# ST-LINK_V2-1.net
KiCad netlist of a schematic drawn in Altium Designer
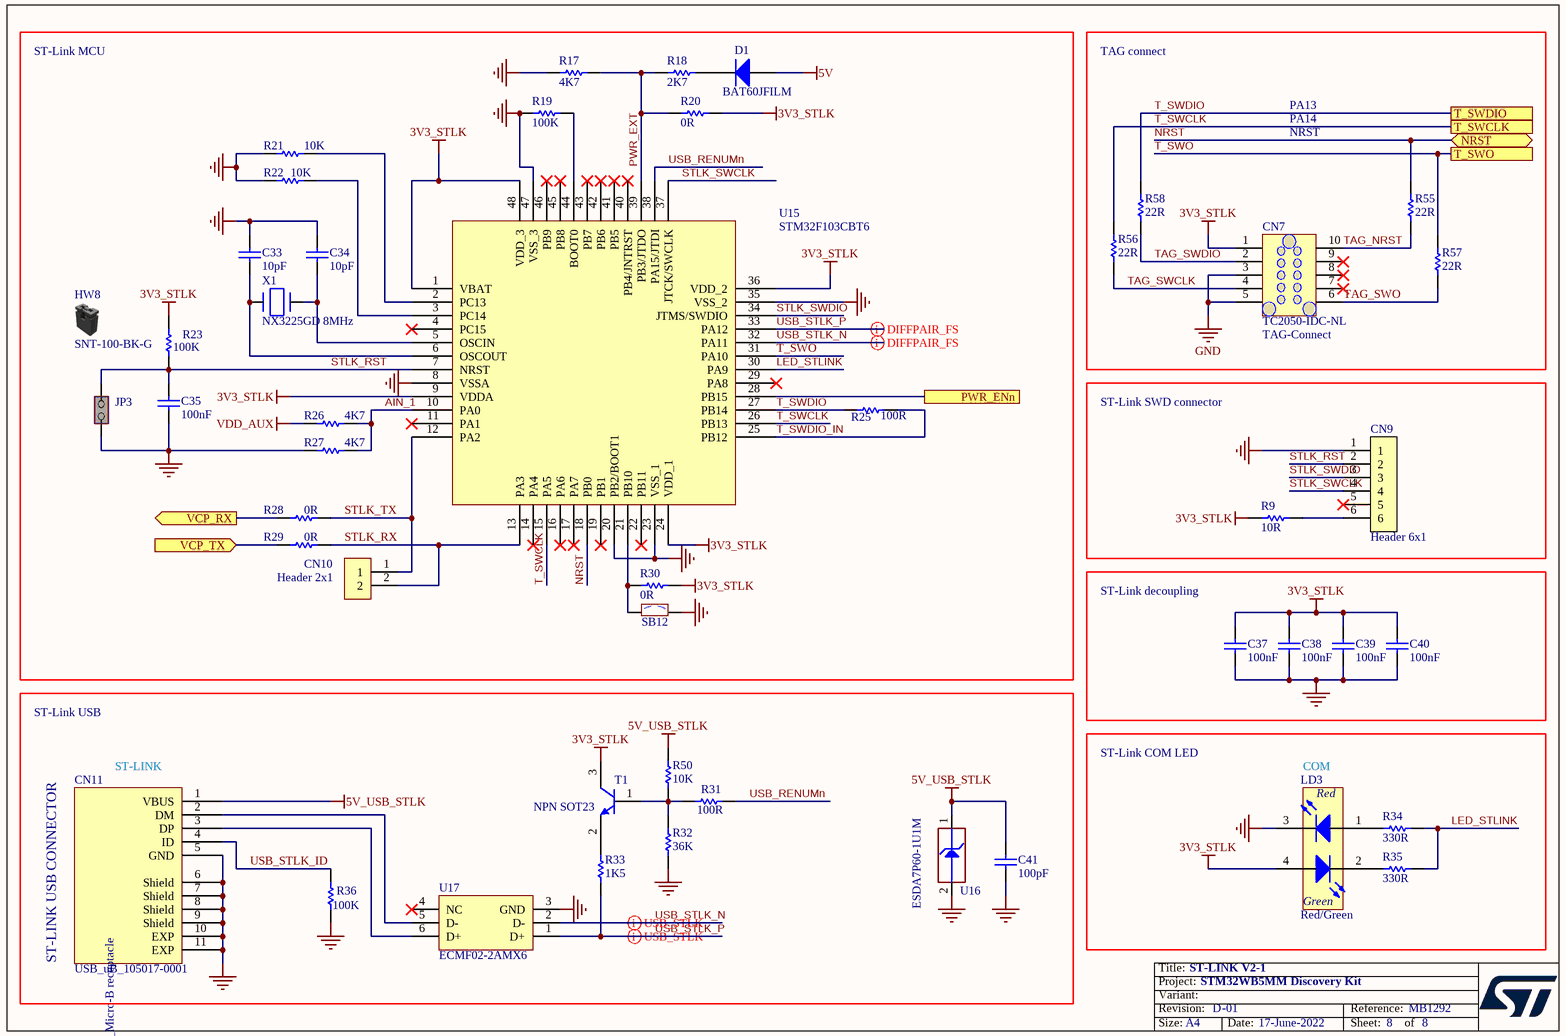
[diagram p0: ST-LINK_V2-1.SchDoc]

(export (version "E")
  (design (tool "Eeschema 10.0.6"))
  (components
    (comp (ref "C33")
      (value "10pF")
      (footprint "C0402")
      (description "Capacitor, MLCC, 10pF, 50V, NPO, +/-5%, 0402, T=0,5mm")
      (fields
        (field (name "INTERNAL_PART_NUMBER") "MCD-00015")
        (field (name "MANUFACTURER_PART_NUMBER") "CC0402JRNPO9BN100")
      )
      (libsource (lib "MCD_PARTS_database") (part "Capacitor"))
    )
    (comp (ref "C34")
      (value "10pF")
      (footprint "C0402")
      (description "Capacitor, MLCC, 10pF, 50V, NPO, +/-5%, 0402, T=0,5mm")
      (fields
        (field (name "INTERNAL_PART_NUMBER") "MCD-00015")
        (field (name "MANUFACTURER_PART_NUMBER") "CC0402JRNPO9BN100")
      )
      (libsource (lib "MCD_PARTS_database") (part "Capacitor"))
    )
    (comp (ref "C35")
      (value "100nF")
      (footprint "C0402")
      (description "Capacitor, MLCC, 100nF, 16V, X7R, +/-10%, 0402, T=0.5mm")
      (fields
        (field (name "INTERNAL_PART_NUMBER") "MCD-00006")
        (field (name "MANUFACTURER_PART_NUMBER") "CC0402KRX7R7BB104")
      )
      (libsource (lib "MCD_PARTS_database") (part "Capacitor"))
    )
    (comp (ref "C37")
      (value "100nF")
      (footprint "C0402")
      (description "Capacitor, MLCC, 100nF, 16V, X7R, +/-10%, 0402, T=0.5mm")
      (fields
        (field (name "INTERNAL_PART_NUMBER") "MCD-00006")
        (field (name "MANUFACTURER_PART_NUMBER") "CC0402KRX7R7BB104")
      )
      (libsource (lib "MCD_PARTS_database") (part "Capacitor"))
    )
    (comp (ref "C38")
      (value "100nF")
      (footprint "C0402")
      (description "Capacitor, MLCC, 100nF, 16V, X7R, +/-10%, 0402, T=0.5mm")
      (fields
        (field (name "INTERNAL_PART_NUMBER") "MCD-00006")
        (field (name "MANUFACTURER_PART_NUMBER") "CC0402KRX7R7BB104")
      )
      (libsource (lib "MCD_PARTS_database") (part "Capacitor"))
    )
    (comp (ref "C39")
      (value "100nF")
      (footprint "C0402")
      (description "Capacitor, MLCC, 100nF, 16V, X7R, +/-10%, 0402, T=0.5mm")
      (fields
        (field (name "INTERNAL_PART_NUMBER") "MCD-00006")
        (field (name "MANUFACTURER_PART_NUMBER") "CC0402KRX7R7BB104")
      )
      (libsource (lib "MCD_PARTS_database") (part "Capacitor"))
    )
    (comp (ref "C40")
      (value "100nF")
      (footprint "C0402")
      (description "Capacitor, MLCC, 100nF, 16V, X7R, +/-10%, 0402, T=0.5mm")
      (fields
        (field (name "INTERNAL_PART_NUMBER") "MCD-00006")
        (field (name "MANUFACTURER_PART_NUMBER") "CC0402KRX7R7BB104")
      )
      (libsource (lib "MCD_PARTS_database") (part "Capacitor"))
    )
    (comp (ref "C41")
      (value "100pF")
      (footprint "C0603_H0P8")
      (description "Capacitor,MLCC,100pF 50V,NPO,+/-5%, 0603,T=0,8mm")
      (fields
        (field (name "INTERNAL_PART_NUMBER") "MCD-01648")
        (field (name "MANUFACTURER_PART_NUMBER") "CC0603JRNPO9BN101")
      )
      (libsource (lib "MCD_PARTS_database") (part "Capacitor"))
    )
    (comp (ref "CN7")
      (value "TC2050-IDC-NL")
      (footprint "CON_TAG-C_TC2050-IDC-NL")
      (description "Tag_Connector Header, 10x2, No legs")
      (fields
        (field (name "INTERNAL_PART_NUMBER") "MCD-00031")
        (field (name "MANUFACTURER_PART_NUMBER") "TC2050-IDC-NL-FP")
      )
      (libsource (lib "MCD_PARTS_database") (part "Tag-10-C"))
    )
    (comp (ref "CN9")
      (value "Header 6x1")
      (footprint "CON_SAMTEC_TSW-106-14-G-S")
      (description "Header 6x1, 2,54mm, height 10.67mm")
      (fields
        (field (name "INTERNAL_PART_NUMBER") "MCD-01592")
        (field (name "MANUFACTURER_PART_NUMBER") "TSW-106-14-G-S")
      )
      (libsource (lib "MCD_PARTS_database") (part "Header 6x1"))
    )
    (comp (ref "CN10")
      (value "Header 2x1")
      (footprint "CON_SAMTEC_TSW-102-07-G-S")
      (description "Header, 2x1, 2,54mm, VR, TH, Height 5.84mm/2.54mm")
      (fields
        (field (name "INTERNAL_PART_NUMBER") "MCD-00032")
        (field (name "MANUFACTURER_PART_NUMBER") "TSW-102-07-G-S")
      )
      (libsource (lib "MCD_PARTS_database") (part "Header 2x1"))
    )
    (comp (ref "CN11")
      (value "USB_uB_105017-0001")
      (footprint "CON_USBMICROB_MOLEX_105017-0001_H2P90")
      (description "USB-MICRO-B, 0.65mm, RA, SMT, Bottom Mount,")
      (fields
        (field (name "INTERNAL_PART_NUMBER") "MCD-00028")
        (field (name "MANUFACTURER_PART_NUMBER") "1050170001")
      )
      (libsource (lib "MCD_PARTS_database") (part "USB_uB_105017.0001"))
    )
    (comp (ref "D1")
      (value "BAT60JFILM")
      (footprint "DIO_SOD323")
      (fields
        (field (name "INTERNAL_PART_NUMBER") "MCD-00034")
        (field (name "MANUFACTURER") "STMICROELECTRONICS")
        (field (name "BMS_PART_NUMBER") "9151097")
      )
      (libsource (lib "MCD_PARTS_database") (part "BAT60JFILM"))
    )
    (comp (ref "HW8")
      (value "SNT-100-BK-G")
      (description "Shunt, 2.54mm, Black, 4.3A, 6.1mm, 5mR")
      (fields (field (name "INTERNAL_PART_NUMBER") "MCD-00122") (field (name "MANUFACTURER") "SAMTEC"))
      (libsource (lib "MCD_PARTS_database") (part "Shunt Black 2.54mm"))
    )
    (comp (ref "JP3")
      (value "Jumper_Header 2x1 Fitted")
      (footprint "CON_SAMTEC_TSW-102-07-G-S")
      (description "Header, 2x1, 2,54mm, VR, TH, Height 5.84mm/2.54mm - Shunt Fitted by default")
      (fields
        (field (name "INTERNAL_PART_NUMBER") "MCD-01904")
        (field (name "MANUFACTURER_PART_NUMBER") "TSW-102-07-G-S")
      )
      (libsource (lib "MCD_PARTS_database") (part "Jumper_Header 2x1 Fitted"))
    )
    (comp (ref "LD3")
      (value "Red/Green")
      (footprint "LED_BI-GR_WE-150141SV73110")
      (description "LED Bicolor, Red/Green, 2V, 20mA, 4-PLCC")
      (fields
        (field (name "INTERNAL_PART_NUMBER") "MCD-02631")
        (field (name "MANUFACTURER") "WURTH ELEKTRONIK")
      )
      (libsource (lib "MCD_PARTS_database") (part "LED_BICOLOR"))
    )
    (comp (ref "R9")
      (value "10R")
      (footprint "R0402")
      (description "Resistor,10R,0402,1%,1/16W")
      (fields
        (field (name "INTERNAL_PART_NUMBER") "MCD-00358")
        (field (name "MANUFACTURER_PART_NUMBER") "RC0402FR-0710RL")
      )
      (libsource (lib "MCD_PARTS_database") (part "Resistor"))
    )
    (comp (ref "R17")
      (value "4K7")
      (footprint "R0402")
      (description "Resistor,4K7,0402,1%,1/16W")
      (fields
        (field (name "INTERNAL_PART_NUMBER") "MCD-00065")
        (field (name "MANUFACTURER_PART_NUMBER") "RC0402FR-074K7L")
      )
      (libsource (lib "MCD_PARTS_database") (part "Resistor"))
    )
    (comp (ref "R18")
      (value "2K7")
      (footprint "R0402")
      (description "Resistor,2K7,0402,1%,1/16W")
      (fields
        (field (name "INTERNAL_PART_NUMBER") "MCD-00055")
        (field (name "MANUFACTURER_PART_NUMBER") "RC0402FR-072K7L")
      )
      (libsource (lib "MCD_PARTS_database") (part "Resistor"))
    )
    (comp (ref "R19")
      (value "100K")
      (footprint "R0402")
      (description "Resistor,100K,0402,1%,1/16W")
      (fields
        (field (name "INTERNAL_PART_NUMBER") "MCD-00059")
        (field (name "MANUFACTURER_PART_NUMBER") "RC0402FR-07100KL")
      )
      (libsource (lib "MCD_PARTS_database") (part "Resistor"))
    )
    (comp (ref "R20")
      (value "0R")
      (footprint "R0402")
      (description "Resistor,0R,0402,5%,1/16W")
      (fields
        (field (name "INTERNAL_PART_NUMBER") "MCD-00052")
        (field (name "MANUFACTURER_PART_NUMBER") "RC0402JR-070RL")
      )
      (libsource (lib "MCD_PARTS_database") (part "Resistor"))
    )
    (comp (ref "R21")
      (value "10K")
      (footprint "R0402")
      (description "Resistor,10K,0402,1%,1/16W")
      (fields
        (field (name "INTERNAL_PART_NUMBER") "MCD-00053")
        (field (name "MANUFACTURER_PART_NUMBER") "RC0402FR-0710KL")
      )
      (libsource (lib "MCD_PARTS_database") (part "Resistor"))
    )
    (comp (ref "R22")
      (value "10K")
      (footprint "R0402")
      (description "Resistor,10K,0402,1%,1/16W")
      (fields
        (field (name "INTERNAL_PART_NUMBER") "MCD-00053")
        (field (name "MANUFACTURER_PART_NUMBER") "RC0402FR-0710KL")
      )
      (libsource (lib "MCD_PARTS_database") (part "Resistor"))
    )
    (comp (ref "R23")
      (value "100K")
      (footprint "R0402")
      (description "Resistor,100K,0402,1%,1/16W")
      (fields
        (field (name "INTERNAL_PART_NUMBER") "MCD-00059")
        (field (name "MANUFACTURER_PART_NUMBER") "RC0402FR-07100KL")
      )
      (libsource (lib "MCD_PARTS_database") (part "Resistor"))
    )
    (comp (ref "R25")
      (value "100R")
      (footprint "R0402")
      (description "Resistor,100R,0402,1%,1/16W")
      (fields
        (field (name "INTERNAL_PART_NUMBER") "MCD-00067")
        (field (name "MANUFACTURER_PART_NUMBER") "RC0402FR-07100RL")
      )
      (libsource (lib "MCD_PARTS_database") (part "Resistor"))
    )
    (comp (ref "R26")
      (value "4K7")
      (footprint "R0402")
      (description "Resistor,4K7,0402,1%,1/16W")
      (fields
        (field (name "INTERNAL_PART_NUMBER") "MCD-00065")
        (field (name "MANUFACTURER_PART_NUMBER") "RC0402FR-074K7L")
      )
      (libsource (lib "MCD_PARTS_database") (part "Resistor"))
    )
    (comp (ref "R27")
      (value "4K7")
      (footprint "R0402")
      (description "Resistor,4K7,0402,1%,1/16W")
      (fields
        (field (name "INTERNAL_PART_NUMBER") "MCD-00065")
        (field (name "MANUFACTURER_PART_NUMBER") "RC0402FR-074K7L")
      )
      (libsource (lib "MCD_PARTS_database") (part "Resistor"))
    )
    (comp (ref "R28")
      (value "0R")
      (footprint "R0402")
      (description "Resistor,0R,0402,5%,1/16W")
      (fields
        (field (name "INTERNAL_PART_NUMBER") "MCD-00052")
        (field (name "MANUFACTURER_PART_NUMBER") "RC0402JR-070RL")
      )
      (libsource (lib "MCD_PARTS_database") (part "Resistor"))
    )
    (comp (ref "R29")
      (value "0R")
      (footprint "R0402")
      (description "Resistor,0R,0402,5%,1/16W")
      (fields
        (field (name "INTERNAL_PART_NUMBER") "MCD-00052")
        (field (name "MANUFACTURER_PART_NUMBER") "RC0402JR-070RL")
      )
      (libsource (lib "MCD_PARTS_database") (part "Resistor"))
    )
    (comp (ref "R30")
      (value "0R")
      (footprint "R0402")
      (description "Resistor,0R,0402,5%,1/16W")
      (fields
        (field (name "INTERNAL_PART_NUMBER") "MCD-00052")
        (field (name "MANUFACTURER_PART_NUMBER") "RC0402JR-070RL")
      )
      (libsource (lib "MCD_PARTS_database") (part "Resistor"))
    )
    (comp (ref "R31")
      (value "100R")
      (footprint "R0402")
      (description "Resistor,100R,0402,1%,1/16W")
      (fields
        (field (name "INTERNAL_PART_NUMBER") "MCD-00067")
        (field (name "MANUFACTURER_PART_NUMBER") "RC0402FR-07100RL")
      )
      (libsource (lib "MCD_PARTS_database") (part "Resistor"))
    )
    (comp (ref "R32")
      (value "36K")
      (footprint "R0402")
      (description "Resistor,36K,0402,1%,1/16W")
      (fields
        (field (name "INTERNAL_PART_NUMBER") "MCD-00069")
        (field (name "MANUFACTURER_PART_NUMBER") "RC0402FR-0736KL")
      )
      (libsource (lib "MCD_PARTS_database") (part "Resistor"))
    )
    (comp (ref "R33")
      (value "1K5")
      (footprint "R0402")
      (description "Resistor,1K5,0402,1%,1/16W")
      (fields
        (field (name "INTERNAL_PART_NUMBER") "MCD-00068")
        (field (name "MANUFACTURER_PART_NUMBER") "RC0402FR-071K5L")
      )
      (libsource (lib "MCD_PARTS_database") (part "Resistor"))
    )
    (comp (ref "R34")
      (value "330R")
      (footprint "R0402")
      (description "Resistor,330R,0402,1%,1/16W")
      (fields
        (field (name "INTERNAL_PART_NUMBER") "MCD-00062")
        (field (name "MANUFACTURER_PART_NUMBER") "RC0402FR-07330RL")
      )
      (libsource (lib "MCD_PARTS_database") (part "Resistor"))
    )
    (comp (ref "R35")
      (value "330R")
      (footprint "R0402")
      (description "Resistor,330R,0402,1%,1/16W")
      (fields
        (field (name "INTERNAL_PART_NUMBER") "MCD-00062")
        (field (name "MANUFACTURER_PART_NUMBER") "RC0402FR-07330RL")
      )
      (libsource (lib "MCD_PARTS_database") (part "Resistor"))
    )
    (comp (ref "R36")
      (value "100K")
      (footprint "R0402")
      (description "Resistor,100K,0402,1%,1/16W")
      (fields
        (field (name "INTERNAL_PART_NUMBER") "MCD-00059")
        (field (name "MANUFACTURER_PART_NUMBER") "RC0402FR-07100KL")
      )
      (libsource (lib "MCD_PARTS_database") (part "Resistor"))
    )
    (comp (ref "R50")
      (value "10K")
      (footprint "R0402")
      (description "Resistor,10K,0402,1%,1/16W")
      (fields
        (field (name "INTERNAL_PART_NUMBER") "MCD-00053")
        (field (name "MANUFACTURER_PART_NUMBER") "RC0402FR-0710KL")
      )
      (libsource (lib "MCD_PARTS_database") (part "Resistor"))
    )
    (comp (ref "R55")
      (value "22R")
      (footprint "R0402")
      (description "Resistor,22R,0402,1%,1/16W")
      (fields
        (field (name "INTERNAL_PART_NUMBER") "MCD-00189")
        (field (name "MANUFACTURER_PART_NUMBER") "RC0402FR-0722RL")
      )
      (libsource (lib "MCD_PARTS_database") (part "Resistor"))
    )
    (comp (ref "R56")
      (value "22R")
      (footprint "R0402")
      (description "Resistor,22R,0402,1%,1/16W")
      (fields
        (field (name "INTERNAL_PART_NUMBER") "MCD-00189")
        (field (name "MANUFACTURER_PART_NUMBER") "RC0402FR-0722RL")
      )
      (libsource (lib "MCD_PARTS_database") (part "Resistor"))
    )
    (comp (ref "R57")
      (value "22R")
      (footprint "R0402")
      (description "Resistor,22R,0402,1%,1/16W")
      (fields
        (field (name "INTERNAL_PART_NUMBER") "MCD-00189")
        (field (name "MANUFACTURER_PART_NUMBER") "RC0402FR-0722RL")
      )
      (libsource (lib "MCD_PARTS_database") (part "Resistor"))
    )
    (comp (ref "R58")
      (value "22R")
      (footprint "R0402")
      (description "Resistor,22R,0402,1%,1/16W")
      (fields
        (field (name "INTERNAL_PART_NUMBER") "MCD-00189")
        (field (name "MANUFACTURER_PART_NUMBER") "RC0402FR-0722RL")
      )
      (libsource (lib "MCD_PARTS_database") (part "Resistor"))
    )
    (comp (ref "SB12")
      (value "SB_OFF")
      (footprint "SOLDER-BRIDGE_R0603-0R")
      (description "Solder Bridge OFF")
      (fields
        (field (name "INTERNAL_PART_NUMBER") "MCD-00072")
        (field (name "MANUFACTURER_PART_NUMBER") "RC0603JR-070RL")
      )
      (libsource (lib "MCD_PARTS_database") (part "SB_OFF"))
    )
    (comp (ref "T1")
      (value "NPN SOT23")
      (footprint "NPN_SOT23")
      (description "NPN Bipolar Transistor")
      (fields
        (field (name "INTERNAL_PART_NUMBER") "MCD-00073")
        (field (name "MANUFACTURER_PART_NUMBER") "BSR14")
      )
      (libsource (lib "MCD_PARTS_database") (part "9013-SOT23"))
    )
    (comp (ref "U15")
      (value "STM32F103CBT6")
      (footprint "ICC_LQFP48_7X7_P050")
      (description "Medium-density performance line ARM-based 32-bit MCU with 128KB Flash")
      (fields
        (field (name "INTERNAL_PART_NUMBER") "MCD-00085")
        (field (name "MANUFACTURER") "STMICROELECTRONICS")
      )
      (libsource (lib "MCD_PARTS_database") (part "STM32F103CBT6"))
    )
    (comp (ref "U16")
      (value "ESDA7P60-1U1M")
      (footprint "ESD_QFN2_1P6X1_P125")
      (description "High power transient voltage suppressor, 7V breakdown")
      (fields
        (field (name "INTERNAL_PART_NUMBER") "MCD-00251")
        (field (name "MANUFACTURER") "STMICROELECTRONICS")
      )
      (libsource (lib "MCD_PARTS_database") (part "ESD-TRANSIL"))
    )
    (comp (ref "U17")
      (value "ECMF02-2AMX6")
      (footprint "ESD_QFN-6L_1P7X1P5_P050")
      (description "Common mode filter with ESD protection for USB 2.0 interface")
      (fields
        (field (name "INTERNAL_PART_NUMBER") "MCD-00649")
        (field (name "MANUFACTURER") "STMICROELECTRONICS")
      )
      (libsource (lib "MCD_PARTS_database") (part "ECMF02-2AMX6"))
    )
    (comp (ref "X1")
      (value "NX3225GD 8MHz")
      (footprint "CRY_NX3225GD_2P")
      (description "Crystal 8MHz, 8pF, +-20ppm, 500ohms max,  SMD")
      (fields
        (field (name "INTERNAL_PART_NUMBER") "MCD-00092")
        (field (name "MANUFACTURER_PART_NUMBER") "NX3225GD 8MHz EXS00A-CG04874")
      )
      (libsource (lib "MCD_PARTS_database") (part "XTAL_2_PINS"))
    )
  )
  (nets
    (net (code "1") (name "/AIN_1") (class "Default")
      (node (ref "R26") (pin "2") (pinfunction "2_2") (pintype "passive"))
      (node (ref "R27") (pin "2") (pinfunction "2_2") (pintype "passive"))
      (node (ref "U15") (pin "10") (pinfunction "PA0_10") (pintype "passive"))
    )
    (net (code "2") (name "/LED_STLINK") (class "Default")
      (node (ref "R34") (pin "2") (pinfunction "2_2") (pintype "passive"))
      (node (ref "R35") (pin "2") (pinfunction "2_2") (pintype "passive"))
      (node (ref "U15") (pin "30") (pinfunction "PA9_30") (pintype "passive"))
    )
    (net (code "3") (name "/NRST") (class "Default")
      (node (ref "R55") (pin "2") (pinfunction "2_2") (pintype "passive"))
      (node (ref "U15") (pin "18") (pinfunction "PB0_18") (pintype "passive"))
    )
    (net (code "4") (name "/PWR_ENn") (class "Default")
      (node (ref "U15") (pin "28") (pinfunction "PB15_28") (pintype "passive"))
    )
    (net (code "5") (name "/PWR_EXT") (class "Default")
      (node (ref "R17") (pin "2") (pinfunction "2_2") (pintype "passive"))
      (node (ref "R18") (pin "1") (pinfunction "1_1") (pintype "passive"))
      (node (ref "R20") (pin "1") (pinfunction "1_1") (pintype "passive"))
      (node (ref "U15") (pin "39") (pinfunction "PB3/JTDO_39") (pintype "passive"))
    )
    (net (code "6") (name "/STLK_RST") (class "Default")
      (node (ref "C35") (pin "2") (pinfunction "2_2") (pintype "passive"))
      (node (ref "CN9") (pin "2") (pinfunction "2_2") (pintype "passive"))
      (node (ref "JP3") (pin "1") (pinfunction "COMMON_1") (pintype "passive"))
      (node (ref "R23") (pin "1") (pinfunction "1_1") (pintype "passive"))
      (node (ref "U15") (pin "7") (pinfunction "NRST_7") (pintype "passive"))
    )
    (net (code "7") (name "/STLK_RX") (class "Default")
      (node (ref "CN10") (pin "2") (pinfunction "2_2") (pintype "passive"))
      (node (ref "R29") (pin "2") (pinfunction "2_2") (pintype "passive"))
      (node (ref "U15") (pin "13") (pinfunction "PA3_13") (pintype "passive"))
    )
    (net (code "8") (name "/STLK_SWCLK") (class "Default")
      (node (ref "CN9") (pin "4") (pinfunction "4_4") (pintype "passive"))
      (node (ref "U15") (pin "37") (pinfunction "JTCK/SWCLK_37") (pintype "passive"))
    )
    (net (code "9") (name "/STLK_SWDIO") (class "Default")
      (node (ref "CN9") (pin "3") (pinfunction "3_3") (pintype "passive"))
      (node (ref "U15") (pin "34") (pinfunction "JTMS/SWDIO_34") (pintype "passive"))
    )
    (net (code "10") (name "/STLK_TX") (class "Default")
      (node (ref "CN10") (pin "1") (pinfunction "1_1") (pintype "passive"))
      (node (ref "R28") (pin "1") (pinfunction "1_1") (pintype "passive"))
      (node (ref "U15") (pin "12") (pinfunction "PA2_12") (pintype "passive"))
    )
    (net (code "11") (name "/TAG_NRST") (class "Default")
      (node (ref "CN7") (pin "10") (pinfunction "10_10") (pintype "passive"))
      (node (ref "R55") (pin "1") (pinfunction "1_1") (pintype "passive"))
    )
    (net (code "12") (name "/TAG_SWCLK") (class "Default")
      (node (ref "CN7") (pin "4") (pinfunction "4_4") (pintype "passive"))
      (node (ref "R56") (pin "1") (pinfunction "1_1") (pintype "passive"))
    )
    (net (code "13") (name "/TAG_SWDIO") (class "Default")
      (node (ref "CN7") (pin "2") (pinfunction "2_2") (pintype "passive"))
      (node (ref "R58") (pin "1") (pinfunction "1_1") (pintype "passive"))
    )
    (net (code "14") (name "/TAG_SWO") (class "Default")
      (node (ref "CN7") (pin "6") (pinfunction "6_6") (pintype "passive"))
      (node (ref "R57") (pin "2") (pinfunction "2_2") (pintype "passive"))
    )
    (net (code "15") (name "/T_SWCLK") (class "Default")
      (node (ref "R56") (pin "2") (pinfunction "2_2") (pintype "passive"))
      (node (ref "U15") (pin "15") (pinfunction "PA5_15") (pintype "passive"))
      (node (ref "U15") (pin "26") (pinfunction "PB13_26") (pintype "passive"))
    )
    (net (code "16") (name "/T_SWDIO") (class "Default")
      (node (ref "R25") (pin "1") (pinfunction "1_1") (pintype "passive"))
      (node (ref "R58") (pin "2") (pinfunction "2_2") (pintype "passive"))
      (node (ref "U15") (pin "27") (pinfunction "PB14_27") (pintype "passive"))
    )
    (net (code "17") (name "/T_SWDIO_IN") (class "Default")
      (node (ref "R25") (pin "2") (pinfunction "2_2") (pintype "passive"))
      (node (ref "U15") (pin "25") (pinfunction "PB12_25") (pintype "passive"))
    )
    (net (code "18") (name "/T_SWO") (class "Default")
      (node (ref "R57") (pin "1") (pinfunction "1_1") (pintype "passive"))
      (node (ref "U15") (pin "31") (pinfunction "PA10_31") (pintype "passive"))
    )
    (net (code "19") (name "/USB_RENUMn") (class "Default")
      (node (ref "R31") (pin "2") (pinfunction "2_2") (pintype "passive"))
      (node (ref "U15") (pin "38") (pinfunction "PA15/JTDI_38") (pintype "passive"))
    )
    (net (code "20") (name "/USB_STLK_ID") (class "Default")
      (node (ref "CN11") (pin "4") (pinfunction "ID_4") (pintype "passive"))
      (node (ref "R36") (pin "2") (pinfunction "2_2") (pintype "passive"))
    )
    (net (code "21") (name "/USB_STLK_N") (class "Default")
      (node (ref "U15") (pin "32") (pinfunction "PA11_32") (pintype "passive"))
      (node (ref "U17") (pin "2") (pinfunction "D-_2") (pintype "passive"))
    )
    (net (code "22") (name "/USB_STLK_P") (class "Default")
      (node (ref "R33") (pin "1") (pinfunction "1_1") (pintype "passive"))
      (node (ref "U15") (pin "33") (pinfunction "PA12_33") (pintype "passive"))
      (node (ref "U17") (pin "1") (pinfunction "D+_1") (pintype "passive"))
    )
    (net (code "23") (name "/VCP_RX") (class "Default")
      (node (ref "R28") (pin "2") (pinfunction "2_2") (pintype "passive"))
    )
    (net (code "24") (name "/VCP_TX") (class "Default")
      (node (ref "R29") (pin "1") (pinfunction "1_1") (pintype "passive"))
    )
    (net (code "25") (name "3V3_STLK") (class "Default")
      (node (ref "C37") (pin "2") (pinfunction "2_2") (pintype "passive"))
      (node (ref "C38") (pin "2") (pinfunction "2_2") (pintype "passive"))
      (node (ref "C39") (pin "2") (pinfunction "2_2") (pintype "passive"))
      (node (ref "C40") (pin "2") (pinfunction "2_2") (pintype "passive"))
      (node (ref "CN7") (pin "1") (pinfunction "1_1") (pintype "passive"))
      (node (ref "LD3") (pin "4") (pinfunction "Green_anode_4") (pintype "passive"))
      (node (ref "R20") (pin "2") (pinfunction "2_2") (pintype "passive"))
      (node (ref "R23") (pin "2") (pinfunction "2_2") (pintype "passive"))
      (node (ref "R30") (pin "2") (pinfunction "2_2") (pintype "passive"))
      (node (ref "R9") (pin "1") (pinfunction "1_1") (pintype "passive"))
      (node (ref "T1") (pin "3") (pinfunction "C_3") (pintype "passive"))
      (node (ref "U15") (pin "1") (pinfunction "VBAT_1") (pintype "passive"))
      (node (ref "U15") (pin "24") (pinfunction "VDD_1_24") (pintype "passive"))
      (node (ref "U15") (pin "36") (pinfunction "VDD_2_36") (pintype "passive"))
      (node (ref "U15") (pin "48") (pinfunction "VDD_3_48") (pintype "passive"))
      (node (ref "U15") (pin "9") (pinfunction "VDDA_9") (pintype "passive"))
    )
    (net (code "26") (name "5V") (class "Default")
      (node (ref "D1") (pin "1") (pinfunction "A_1") (pintype "passive"))
    )
    (net (code "27") (name "5V_USB_STLK") (class "Default")
      (node (ref "C41") (pin "1") (pinfunction "1_1") (pintype "passive"))
      (node (ref "CN11") (pin "1") (pinfunction "VBUS_1") (pintype "passive"))
      (node (ref "R50") (pin "2") (pinfunction "2_2") (pintype "passive"))
      (node (ref "U16") (pin "1") (pinfunction "IO1_1") (pintype "passive"))
    )
    (net (code "28") (name "GND") (class "Default")
      (node (ref "C33") (pin "2") (pinfunction "2_2") (pintype "passive"))
      (node (ref "C34") (pin "2") (pinfunction "2_2") (pintype "passive"))
      (node (ref "C35") (pin "1") (pinfunction "1_1") (pintype "passive"))
      (node (ref "C37") (pin "1") (pinfunction "1_1") (pintype "passive"))
      (node (ref "C38") (pin "1") (pinfunction "1_1") (pintype "passive"))
      (node (ref "C39") (pin "1") (pinfunction "1_1") (pintype "passive"))
      (node (ref "C40") (pin "1") (pinfunction "1_1") (pintype "passive"))
      (node (ref "C41") (pin "2") (pinfunction "2_2") (pintype "passive"))
      (node (ref "CN11") (pin "10") (pinfunction "EXP_10") (pintype "passive"))
      (node (ref "CN11") (pin "11") (pinfunction "EXP_11") (pintype "passive"))
      (node (ref "CN11") (pin "5") (pinfunction "GND_5") (pintype "passive"))
      (node (ref "CN11") (pin "6") (pinfunction "Shield_6") (pintype "passive"))
      (node (ref "CN11") (pin "7") (pinfunction "Shield_7") (pintype "passive"))
      (node (ref "CN11") (pin "8") (pinfunction "Shield_8") (pintype "passive"))
      (node (ref "CN11") (pin "9") (pinfunction "Shield_9") (pintype "passive"))
      (node (ref "CN7") (pin "3") (pinfunction "3_3") (pintype "passive"))
      (node (ref "CN7") (pin "5") (pinfunction "5_5") (pintype "passive"))
      (node (ref "CN9") (pin "1") (pinfunction "1_1") (pintype "passive"))
      (node (ref "JP3") (pin "2") (pinfunction "NO_2") (pintype "passive"))
      (node (ref "LD3") (pin "3") (pinfunction "RED_cathode_3") (pintype "passive"))
      (node (ref "R17") (pin "1") (pinfunction "1_1") (pintype "passive"))
      (node (ref "R19") (pin "1") (pinfunction "1_1") (pintype "passive"))
      (node (ref "R21") (pin "2") (pinfunction "2_2") (pintype "passive"))
      (node (ref "R22") (pin "1") (pinfunction "1_1") (pintype "passive"))
      (node (ref "R27") (pin "1") (pinfunction "1_1") (pintype "passive"))
      (node (ref "R32") (pin "1") (pinfunction "1_1") (pintype "passive"))
      (node (ref "R36") (pin "1") (pinfunction "1_1") (pintype "passive"))
      (node (ref "SB12") (pin "2") (pinfunction "2_2") (pintype "passive"))
      (node (ref "U15") (pin "20") (pinfunction "PB2/BOOT1_20") (pintype "passive"))
      (node (ref "U15") (pin "23") (pinfunction "VSS_1_23") (pintype "passive"))
      (node (ref "U15") (pin "35") (pinfunction "VSS_2_35") (pintype "passive"))
      (node (ref "U15") (pin "47") (pinfunction "VSS_3_47") (pintype "passive"))
      (node (ref "U15") (pin "8") (pinfunction "VSSA_8") (pintype "passive"))
      (node (ref "U16") (pin "2") (pinfunction "GND_2") (pintype "passive"))
      (node (ref "U17") (pin "3") (pinfunction "GND_3") (pintype "passive"))
    )
    (net (code "29") (name "Net-(CN9-Pad6)") (class "Default")
      (node (ref "CN9") (pin "6") (pinfunction "6_6") (pintype "passive"))
      (node (ref "R9") (pin "2") (pinfunction "2_2") (pintype "passive"))
    )
    (net (code "30") (name "Net-(CN11-DM)") (class "Default")
      (node (ref "CN11") (pin "2") (pinfunction "DM_2") (pintype "passive"))
      (node (ref "U17") (pin "5") (pinfunction "D-_5") (pintype "passive"))
    )
    (net (code "31") (name "Net-(CN11-DP)") (class "Default")
      (node (ref "CN11") (pin "3") (pinfunction "DP_3") (pintype "passive"))
      (node (ref "U17") (pin "6") (pinfunction "D+_6") (pintype "passive"))
    )
    (net (code "32") (name "Net-(D1-K)") (class "Default")
      (node (ref "D1") (pin "2") (pinfunction "K_2") (pintype "passive"))
      (node (ref "R18") (pin "2") (pinfunction "2_2") (pintype "passive"))
    )
    (net (code "33") (name "Net-(LD3-Green_cathode)") (class "Default")
      (node (ref "LD3") (pin "2") (pinfunction "Green_cathode_2") (pintype "passive"))
      (node (ref "R35") (pin "1") (pinfunction "1_1") (pintype "passive"))
    )
    (net (code "34") (name "Net-(LD3-Red_anode)") (class "Default")
      (node (ref "LD3") (pin "1") (pinfunction "Red_anode_1") (pintype "passive"))
      (node (ref "R34") (pin "1") (pinfunction "1_1") (pintype "passive"))
    )
    (net (code "35") (name "Net-(T1-B)") (class "Default")
      (node (ref "R31") (pin "1") (pinfunction "1_1") (pintype "passive"))
      (node (ref "R32") (pin "2") (pinfunction "2_2") (pintype "passive"))
      (node (ref "R50") (pin "1") (pinfunction "1_1") (pintype "passive"))
      (node (ref "T1") (pin "1") (pinfunction "B_1") (pintype "passive"))
    )
    (net (code "36") (name "Net-(T1-E)") (class "Default")
      (node (ref "R33") (pin "2") (pinfunction "2_2") (pintype "passive"))
      (node (ref "T1") (pin "2") (pinfunction "E_2") (pintype "passive"))
    )
    (net (code "37") (name "Net-(U15-BOOT0)") (class "Default")
      (node (ref "R19") (pin "2") (pinfunction "2_2") (pintype "passive"))
      (node (ref "U15") (pin "44") (pinfunction "BOOT0_44") (pintype "passive"))
    )
    (net (code "38") (name "Net-(U15-OSCIN)") (class "Default")
      (node (ref "C34") (pin "1") (pinfunction "1_1") (pintype "passive"))
      (node (ref "U15") (pin "5") (pinfunction "OSCIN_5") (pintype "passive"))
      (node (ref "X1") (pin "1") (pinfunction "X1_1") (pintype "passive"))
    )
    (net (code "39") (name "Net-(U15-OSCOUT)") (class "Default")
      (node (ref "C33") (pin "1") (pinfunction "1_1") (pintype "passive"))
      (node (ref "U15") (pin "6") (pinfunction "OSCOUT_6") (pintype "passive"))
      (node (ref "X1") (pin "2") (pinfunction "X2_2") (pintype "passive"))
    )
    (net (code "40") (name "Net-(U15-PB10)") (class "Default")
      (node (ref "R30") (pin "1") (pinfunction "1_1") (pintype "passive"))
      (node (ref "SB12") (pin "1") (pinfunction "1_1") (pintype "passive"))
      (node (ref "U15") (pin "21") (pinfunction "PB10_21") (pintype "passive"))
    )
    (net (code "41") (name "Net-(U15-PC13)") (class "Default")
      (node (ref "R21") (pin "1") (pinfunction "1_1") (pintype "passive"))
      (node (ref "U15") (pin "2") (pinfunction "PC13_2") (pintype "passive"))
    )
    (net (code "42") (name "Net-(U15-PC14)") (class "Default")
      (node (ref "R22") (pin "2") (pinfunction "2_2") (pintype "passive"))
      (node (ref "U15") (pin "3") (pinfunction "PC14_3") (pintype "passive"))
    )
    (net (code "43") (name "VDD_AUX") (class "Default")
      (node (ref "R26") (pin "1") (pinfunction "1_1") (pintype "passive"))
    )
    (net (code "44") (name "unconnected-(CN7-Pad7)") (class "Default")
      (node (ref "CN7") (pin "7") (pinfunction "7_7") (pintype "passive+no_connect"))
    )
    (net (code "45") (name "unconnected-(CN7-Pad8)") (class "Default")
      (node (ref "CN7") (pin "8") (pinfunction "8_8") (pintype "passive+no_connect"))
    )
    (net (code "46") (name "unconnected-(CN7-Pad9)") (class "Default")
      (node (ref "CN7") (pin "9") (pinfunction "9_9") (pintype "passive+no_connect"))
    )
    (net (code "47") (name "unconnected-(CN9-Pad5)") (class "Default")
      (node (ref "CN9") (pin "5") (pinfunction "5_5") (pintype "passive+no_connect"))
    )
    (net (code "48") (name "unconnected-(U15-PA1-Pad11)") (class "Default")
      (node (ref "U15") (pin "11") (pinfunction "PA1_11") (pintype "passive+no_connect"))
    )
    (net (code "49") (name "unconnected-(U15-PA4-Pad14)") (class "Default")
      (node (ref "U15") (pin "14") (pinfunction "PA4_14") (pintype "passive+no_connect"))
    )
    (net (code "50") (name "unconnected-(U15-PA6-Pad16)") (class "Default")
      (node (ref "U15") (pin "16") (pinfunction "PA6_16") (pintype "passive+no_connect"))
    )
    (net (code "51") (name "unconnected-(U15-PA7-Pad17)") (class "Default")
      (node (ref "U15") (pin "17") (pinfunction "PA7_17") (pintype "passive+no_connect"))
    )
    (net (code "52") (name "unconnected-(U15-PA8-Pad29)") (class "Default")
      (node (ref "U15") (pin "29") (pinfunction "PA8_29") (pintype "passive+no_connect"))
    )
    (net (code "53") (name "unconnected-(U15-PB1-Pad19)") (class "Default")
      (node (ref "U15") (pin "19") (pinfunction "PB1_19") (pintype "passive+no_connect"))
    )
    (net (code "54") (name "unconnected-(U15-PB4{slash}JNTRST-Pad40)") (class "Default")
      (node (ref "U15") (pin "40") (pinfunction "PB4/JNTRST_40") (pintype "passive+no_connect"))
    )
    (net (code "55") (name "unconnected-(U15-PB5-Pad41)") (class "Default")
      (node (ref "U15") (pin "41") (pinfunction "PB5_41") (pintype "passive+no_connect"))
    )
    (net (code "56") (name "unconnected-(U15-PB6-Pad42)") (class "Default")
      (node (ref "U15") (pin "42") (pinfunction "PB6_42") (pintype "passive+no_connect"))
    )
    (net (code "57") (name "unconnected-(U15-PB7-Pad43)") (class "Default")
      (node (ref "U15") (pin "43") (pinfunction "PB7_43") (pintype "passive+no_connect"))
    )
    (net (code "58") (name "unconnected-(U15-PB8-Pad45)") (class "Default")
      (node (ref "U15") (pin "45") (pinfunction "PB8_45") (pintype "passive+no_connect"))
    )
    (net (code "59") (name "unconnected-(U15-PB9-Pad46)") (class "Default")
      (node (ref "U15") (pin "46") (pinfunction "PB9_46") (pintype "passive+no_connect"))
    )
    (net (code "60") (name "unconnected-(U15-PB11-Pad22)") (class "Default")
      (node (ref "U15") (pin "22") (pinfunction "PB11_22") (pintype "passive+no_connect"))
    )
    (net (code "61") (name "unconnected-(U15-PC15-Pad4)") (class "Default")
      (node (ref "U15") (pin "4") (pinfunction "PC15_4") (pintype "passive+no_connect"))
    )
    (net (code "62") (name "unconnected-(U17-NC-Pad4)") (class "Default")
      (node (ref "U17") (pin "4") (pinfunction "NC_4") (pintype "passive+no_connect"))
    )
  )
)
